# TSOC_PSoC4L.net
KiCad netlist of a schematic drawn in EAGLE
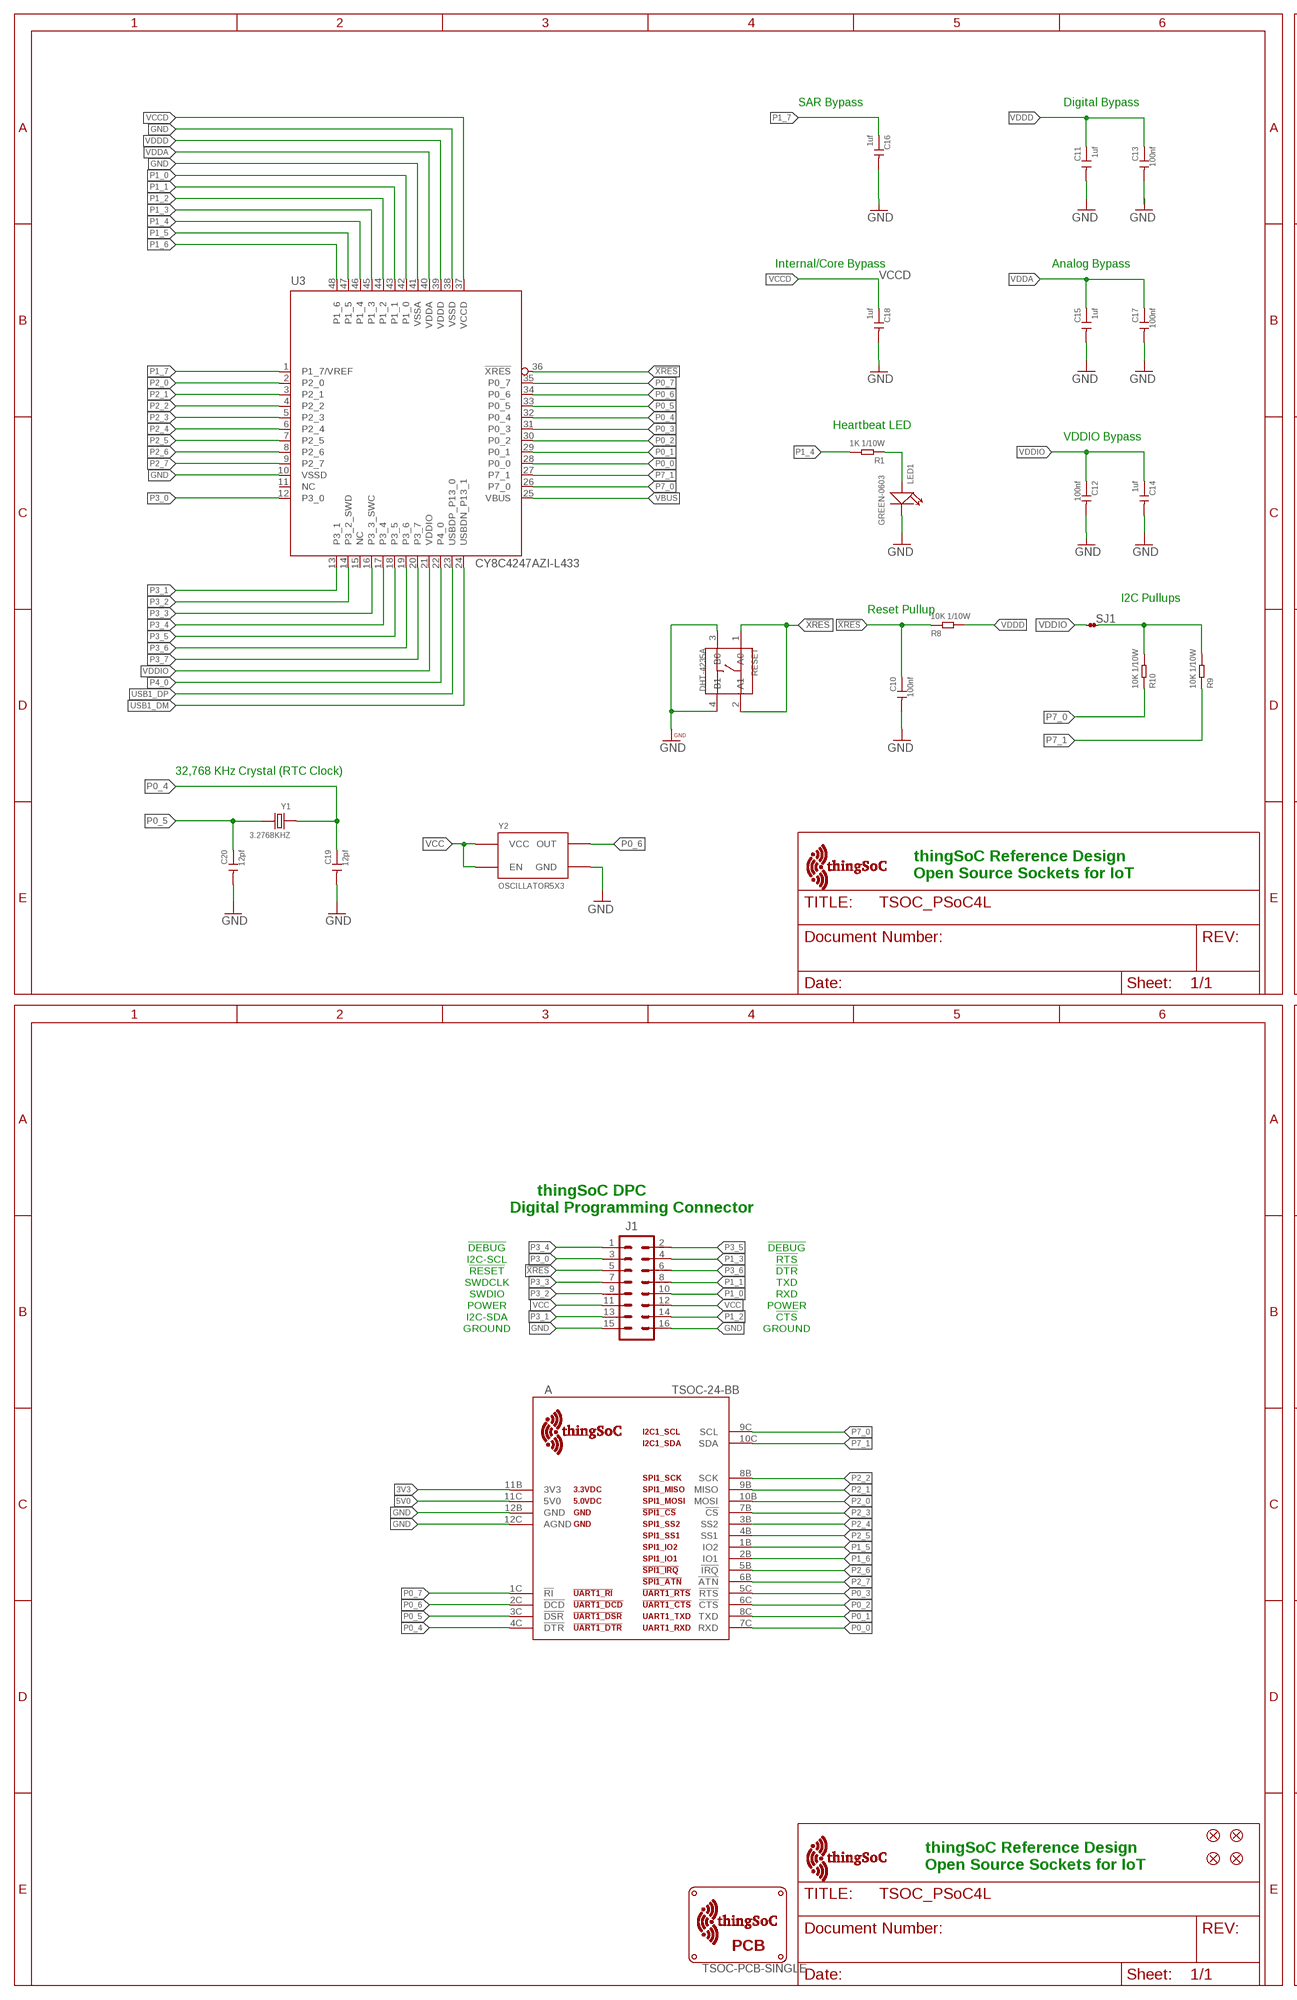
[diagram p0: schematic, sheet 1, part 1 of 2]
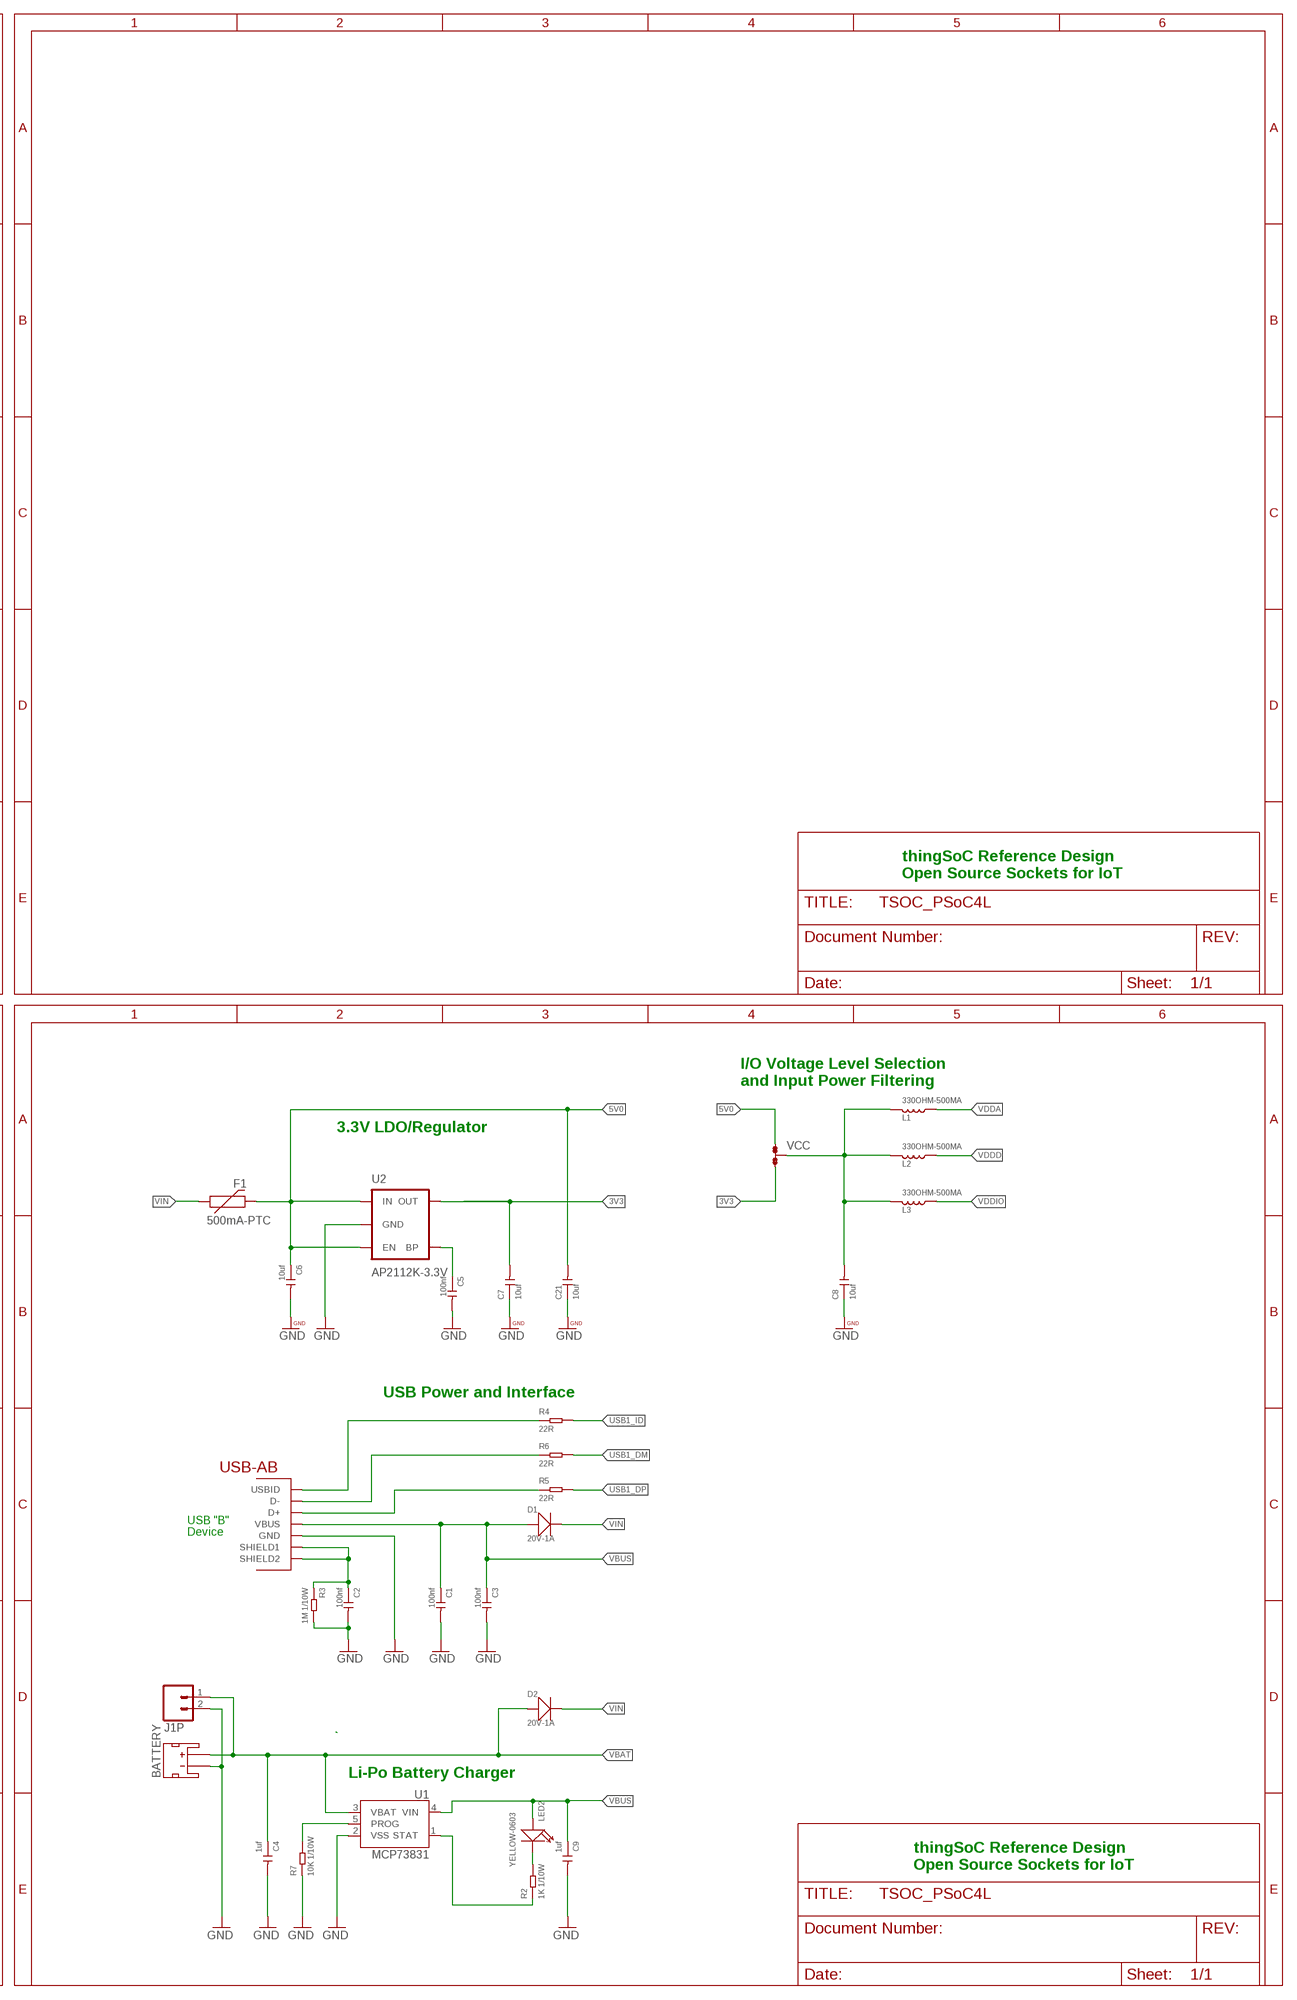
[diagram p1: schematic, sheet 1, part 2 of 2]

(export (version "E")
  (design (tool "Eeschema 10.0.6"))
  (components
    (comp (ref "A")
      (value "TSOC-24-BB")
      (footprint "eagle-import:TSOC-BB-S24")
      (libsource (lib "eagle-import") (part "TSOC-24-BB"))
    )
    (comp (ref "BATTERY")
      (value "JST_2MM_MALE")
      (footprint "eagle-import:JST-2-SMD")
      (libsource (lib "eagle-import") (part "JST_2MM_MALE"))
    )
    (comp (ref "C1")
      (value "100nf")
      (footprint "eagle-import:C0603")
      (fields (field (name "MPN") "CC0603KRX7R9BB104"))
      (libsource (lib "eagle-import") (part "CERAMIC-100NF-50V-10%-X7R(0603)"))
    )
    (comp (ref "C2")
      (value "100nf")
      (footprint "eagle-import:C0603")
      (fields (field (name "MPN") "CC0603KRX7R9BB104"))
      (libsource (lib "eagle-import") (part "CERAMIC-100NF-50V-10%-X7R(0603)"))
    )
    (comp (ref "C3")
      (value "100nf")
      (footprint "eagle-import:C0603")
      (fields (field (name "MPN") "CC0603KRX7R9BB104"))
      (libsource (lib "eagle-import") (part "CERAMIC-100NF-50V-10%-X7R(0603)"))
    )
    (comp (ref "C4")
      (value "1uf")
      (footprint "eagle-import:C0603")
      (fields (field (name "MPN") "CC0603KRX7R8BB105"))
      (libsource (lib "eagle-import") (part "CERAMIC-1UF-25V-10%-X7R(0603)"))
    )
    (comp (ref "C5")
      (value "100nf")
      (footprint "eagle-import:C0603")
      (fields (field (name "MPN") "CC0603KRX7R9BB104"))
      (libsource (lib "eagle-import") (part "CERAMIC-100NF-50V-10%-X7R(0603)"))
    )
    (comp (ref "C6")
      (value "10uf")
      (footprint "eagle-import:C0603")
      (fields (field (name "MPN") "CC0603KRX5R6BB106"))
      (libsource (lib "eagle-import") (part "CERAMIC-10UF-10V-10%-X5R(0603)"))
    )
    (comp (ref "C7")
      (value "10uf")
      (footprint "eagle-import:C0603")
      (fields (field (name "MPN") "CC0603KRX5R6BB106"))
      (libsource (lib "eagle-import") (part "CERAMIC-10UF-10V-10%-X5R(0603)"))
    )
    (comp (ref "C8")
      (value "10uf")
      (footprint "eagle-import:C0603")
      (fields (field (name "MPN") "CC0603KRX5R6BB106"))
      (libsource (lib "eagle-import") (part "CERAMIC-10UF-10V-10%-X5R(0603)"))
    )
    (comp (ref "C9")
      (value "1uf")
      (footprint "eagle-import:C0603")
      (fields (field (name "MPN") "CC0603KRX7R8BB105"))
      (libsource (lib "eagle-import") (part "CERAMIC-1UF-25V-10%-X7R(0603)"))
    )
    (comp (ref "C10")
      (value "100nf")
      (footprint "eagle-import:C0603")
      (fields (field (name "MPN") "CC0603KRX7R9BB104"))
      (libsource (lib "eagle-import") (part "CERAMIC-100NF-50V-10%-X7R(0603)"))
    )
    (comp (ref "C11")
      (value "1uf")
      (footprint "eagle-import:C0603")
      (fields (field (name "MPN") "CC0603KRX7R8BB105"))
      (libsource (lib "eagle-import") (part "CERAMIC-1UF-25V-10%-X7R(0603)"))
    )
    (comp (ref "C12")
      (value "100nf")
      (footprint "eagle-import:C0603")
      (fields (field (name "MPN") "CC0603KRX7R9BB104"))
      (libsource (lib "eagle-import") (part "CERAMIC-100NF-50V-10%-X7R(0603)"))
    )
    (comp (ref "C13")
      (value "100nf")
      (footprint "eagle-import:C0603")
      (fields (field (name "MPN") "CC0603KRX7R9BB104"))
      (libsource (lib "eagle-import") (part "CERAMIC-100NF-50V-10%-X7R(0603)"))
    )
    (comp (ref "C14")
      (value "1uf")
      (footprint "eagle-import:C0603")
      (fields (field (name "MPN") "CC0603KRX7R8BB105"))
      (libsource (lib "eagle-import") (part "CERAMIC-1UF-25V-10%-X7R(0603)"))
    )
    (comp (ref "C15")
      (value "1uf")
      (footprint "eagle-import:C0603")
      (fields (field (name "MPN") "CC0603KRX7R8BB105"))
      (libsource (lib "eagle-import") (part "CERAMIC-1UF-25V-10%-X7R(0603)"))
    )
    (comp (ref "C16")
      (value "1uf")
      (footprint "eagle-import:C0603")
      (fields (field (name "MPN") "CC0603KRX7R8BB105"))
      (libsource (lib "eagle-import") (part "CERAMIC-1UF-25V-10%-X7R(0603)"))
    )
    (comp (ref "C17")
      (value "100nf")
      (footprint "eagle-import:C0603")
      (fields (field (name "MPN") "CC0603KRX7R9BB104"))
      (libsource (lib "eagle-import") (part "CERAMIC-100NF-50V-10%-X7R(0603)"))
    )
    (comp (ref "C18")
      (value "1uf")
      (footprint "eagle-import:C0603")
      (fields (field (name "MPN") "CC0603KRX7R8BB105"))
      (libsource (lib "eagle-import") (part "CERAMIC-1UF-25V-10%-X7R(0603)"))
    )
    (comp (ref "C19")
      (value "12pf")
      (footprint "eagle-import:C0603")
      (fields (field (name "MPN") "CC0603JRNPO9BN120"))
      (libsource (lib "eagle-import") (part "CERAMIC-12PF-50V-5%-NPO(0603)"))
    )
    (comp (ref "C20")
      (value "12pf")
      (footprint "eagle-import:C0603")
      (fields (field (name "MPN") "CC0603JRNPO9BN120"))
      (libsource (lib "eagle-import") (part "CERAMIC-12PF-50V-5%-NPO(0603)"))
    )
    (comp (ref "C21")
      (value "10uf")
      (footprint "eagle-import:C0603")
      (fields (field (name "MPN") "CC0603KRX5R6BB106"))
      (libsource (lib "eagle-import") (part "CERAMIC-10UF-10V-10%-X5R(0603)"))
    )
    (comp (ref "D1")
      (value "20V-1A")
      (footprint "eagle-import:SOD-123")
      (fields (field (name "MPN") "B5819W"))
      (libsource (lib "eagle-import") (part "SMD-DIODE-SCHOTTKY-20V-1A(SOD-123)"))
    )
    (comp (ref "D2")
      (value "20V-1A")
      (footprint "eagle-import:SOD-123")
      (fields (field (name "MPN") "B5819W"))
      (libsource (lib "eagle-import") (part "SMD-DIODE-SCHOTTKY-20V-1A(SOD-123)"))
    )
    (comp (ref "F1")
      (value "500mA-PTC")
      (footprint "eagle-import:PTC-1206")
      (libsource (lib "eagle-import") (part "PTCSMD"))
    )
    (comp (ref "FID1")
      (value "FIDUCIALUFIDUCIAL")
      (footprint "eagle-import:MICRO-FIDUCIAL")
      (libsource (lib "eagle-import") (part "FIDUCIALUFIDUCIAL"))
    )
    (comp (ref "FID2")
      (value "FIDUCIALUFIDUCIAL")
      (footprint "eagle-import:MICRO-FIDUCIAL")
      (libsource (lib "eagle-import") (part "FIDUCIALUFIDUCIAL"))
    )
    (comp (ref "FID3")
      (value "FIDUCIALUFIDUCIAL")
      (footprint "eagle-import:MICRO-FIDUCIAL")
      (libsource (lib "eagle-import") (part "FIDUCIALUFIDUCIAL"))
    )
    (comp (ref "FID4")
      (value "FIDUCIALUFIDUCIAL")
      (footprint "eagle-import:MICRO-FIDUCIAL")
      (libsource (lib "eagle-import") (part "FIDUCIALUFIDUCIAL"))
    )
    (comp (ref "J1")
      (value "M08X2")
      (footprint "eagle-import:2X8")
      (libsource (lib "eagle-import") (part "M08X2"))
    )
    (comp (ref "J1P")
      (value "M02-JST-2-PTH-NO_SILK")
      (footprint "eagle-import:JST-2-PTH-NS")
      (libsource (lib "eagle-import") (part "M02-JST-2-PTH-NO_SILK"))
    )
    (comp (ref "L1")
      (value "330OHM-500MA")
      (footprint "eagle-import:L0603")
      (fields (field (name "MPN") "BLM18AG121SN1D"))
      (libsource (lib "eagle-import") (part "SMD-FERRITE-CHIP-120-OHM-500MA(0603)"))
    )
    (comp (ref "L2")
      (value "330OHM-500MA")
      (footprint "eagle-import:L0603")
      (fields (field (name "MPN") "BLM18AG121SN1D"))
      (libsource (lib "eagle-import") (part "SMD-FERRITE-CHIP-120-OHM-500MA(0603)"))
    )
    (comp (ref "L3")
      (value "330OHM-500MA")
      (footprint "eagle-import:L0603")
      (fields (field (name "MPN") "BLM18AG121SN1D"))
      (libsource (lib "eagle-import") (part "SMD-FERRITE-CHIP-120-OHM-500MA(0603)"))
    )
    (comp (ref "LED1")
      (value "GREEN-0603")
      (footprint "eagle-import:LED-0603")
      (fields (field (name "MPN") "19-217-G7C-AN1P2-3T"))
      (libsource (lib "eagle-import") (part "SMD-LED-CLEAR-GREEN(0603)"))
    )
    (comp (ref "LED2")
      (value "YELLOW-0603")
      (footprint "eagle-import:LED-0603")
      (fields (field (name "MPN") "19-217-Y5C-AM1N1VY-3T"))
      (libsource (lib "eagle-import") (part "SMD-LED-CLEAR-YELLOW(0603)"))
    )
    (comp (ref "R1")
      (value "1K 1/10W")
      (footprint "eagle-import:R0603")
      (fields (field (name "MPN") "RC0603JR-071KL"))
      (libsource (lib "eagle-import") (part "SMD-RES-1K-5%-1/10W(0603)"))
    )
    (comp (ref "R2")
      (value "1K 1/10W")
      (footprint "eagle-import:R0603")
      (fields (field (name "MPN") "RC0603JR-071KL"))
      (libsource (lib "eagle-import") (part "SMD-RES-1K-5%-1/10W(0603)"))
    )
    (comp (ref "R3")
      (value "1M 1/10W")
      (footprint "eagle-import:R0603")
      (fields (field (name "MPN") "RC0603JR-071ML"))
      (libsource (lib "eagle-import") (part "SMD-RES-1M-5%-1/10W(0603)"))
    )
    (comp (ref "R4")
      (value "22R")
      (footprint "eagle-import:R0603")
      (fields (field (name "MPN") "RC0603JR-0722RL"))
      (libsource (lib "eagle-import") (part "SMD-RES-22R-5%-1/10W(0603)"))
    )
    (comp (ref "R5")
      (value "22R")
      (footprint "eagle-import:R0603")
      (fields (field (name "MPN") "RC0603JR-0722RL"))
      (libsource (lib "eagle-import") (part "SMD-RES-22R-5%-1/10W(0603)"))
    )
    (comp (ref "R6")
      (value "22R")
      (footprint "eagle-import:R0603")
      (fields (field (name "MPN") "RC0603JR-0722RL"))
      (libsource (lib "eagle-import") (part "SMD-RES-22R-5%-1/10W(0603)"))
    )
    (comp (ref "R7")
      (value "10K 1/10W")
      (footprint "eagle-import:R0603")
      (fields (field (name "MPN") "RC0603JR-0710KL"))
      (libsource (lib "eagle-import") (part "SMD-RES-10K-5%-1/10W(0603)"))
    )
    (comp (ref "R8")
      (value "10K 1/10W")
      (footprint "eagle-import:R0603")
      (fields (field (name "MPN") "RC0603JR-0710KL"))
      (libsource (lib "eagle-import") (part "SMD-RES-10K-5%-1/10W(0603)"))
    )
    (comp (ref "R9")
      (value "10K 1/10W")
      (footprint "eagle-import:R0603")
      (fields (field (name "MPN") "RC0603JR-0710KL"))
      (libsource (lib "eagle-import") (part "SMD-RES-10K-5%-1/10W(0603)"))
    )
    (comp (ref "R10")
      (value "10K 1/10W")
      (footprint "eagle-import:R0603")
      (fields (field (name "MPN") "RC0603JR-0710KL"))
      (libsource (lib "eagle-import") (part "SMD-RES-10K-5%-1/10W(0603)"))
    )
    (comp (ref "RESET")
      (value "DHT-4235A")
      (footprint "eagle-import:SW4-SMD-4.2X3.2X2.5MM")
      (libsource (lib "eagle-import") (part "SMD-BUTTON-TOP-DHT-4235A(4P-4.2X3.2MM)"))
    )
    (comp (ref "SJ1")
      (value "JMP-2-NC")
      (footprint "eagle-import:JMP-2-NC")
      (libsource (lib "eagle-import") (part "JMP-2-NC"))
    )
    (comp (ref "U$6")
      (value "TSOC-PCB-SINGLE")
      (footprint "eagle-import:TSOC-BB-BRD-DIM")
      (libsource (lib "eagle-import") (part "TSOC-PCB-SINGLE"))
    )
    (comp (ref "U$100")
      (value "TSOC-LOGO-SMALL")
      (footprint "eagle-import:TSOC-LOGO-SML")
      (libsource (lib "eagle-import") (part "TSOC-LOGO-SMALL"))
    )
    (comp (ref "U$101")
      (value "TSOC-LOGO-LRG")
      (footprint "eagle-import:TSOC-LOGO-LRG")
      (libsource (lib "eagle-import") (part "TSOC-LOGO-LRG"))
    )
    (comp (ref "U1")
      (value "MCP73831")
      (footprint "eagle-import:SOT23-5")
      (libsource (lib "eagle-import") (part "MCP73831"))
    )
    (comp (ref "U2")
      (value "AP2112K-3.3V")
      (footprint "eagle-import:SOT23-5")
      (libsource (lib "eagle-import") (part "V_REG_LDOSMD"))
    )
    (comp (ref "U3")
      (value "CY8C4247AZI-L433")
      (footprint "eagle-import:TQFP-7X7-48")
      (libsource (lib "eagle-import") (part "CY8C4247AZI-L433"))
    )
    (comp (ref "USB")
      (value "USB_AB")
      (footprint "eagle-import:USB-AB-MICRO-SMD")
      (libsource (lib "eagle-import") (part "USB_AB"))
    )
    (comp (ref "VCC")
      (value "JMP-3-1_2")
      (footprint "eagle-import:JMP-3-1_2")
      (libsource (lib "eagle-import") (part "JMP-3-1_2"))
    )
    (comp (ref "Y1")
      (value "3.2768KHZ")
      (footprint "eagle-import:X2-SMD-L2.0X1.2X0.55MM")
      (fields (field (name "MPN") "FC-12M"))
      (libsource (lib "eagle-import") (part "SMD-CRYSTAL-32.768KHZ-12.5PF-20PPM-90K(2P-L2.0X1.2MM)"))
    )
    (comp (ref "Y2")
      (value "OSCILLATOR5X3")
      (footprint "eagle-import:CRYSTAL-SMD-5X3")
      (libsource (lib "eagle-import") (part "OSCILLATOR5X3"))
    )
  )
  (nets
    (net (code "1") (name "/~{XRES}") (class "Default")
      (node (ref "C10") (pin "1") (pinfunction "1_1") (pintype "passive"))
      (node (ref "J1") (pin "5") (pinfunction "5_5") (pintype "passive"))
      (node (ref "R8") (pin "1") (pinfunction "1_1") (pintype "passive"))
      (node (ref "RESET") (pin "1") (pinfunction "A0_1") (pintype "bidirectional"))
      (node (ref "RESET") (pin "2") (pinfunction "A1_2") (pintype "bidirectional"))
      (node (ref "U3") (pin "36") (pinfunction "~{XRES}_36") (pintype "bidirectional"))
    )
    (net (code "2") (name "3V3") (class "Default")
      (node (ref "A") (pin "11B") (pinfunction "3V3_11B") (pintype "bidirectional"))
      (node (ref "C7") (pin "2") (pinfunction "2_2") (pintype "passive"))
      (node (ref "U2") (pin "5") (pinfunction "OUT_5") (pintype "passive"))
      (node (ref "VCC") (pin "3") (pinfunction "3_3") (pintype "passive"))
    )
    (net (code "3") (name "5V0") (class "Default")
      (node (ref "A") (pin "11C") (pinfunction "5V0_11C") (pintype "bidirectional"))
      (node (ref "C21") (pin "2") (pinfunction "2_2") (pintype "passive"))
      (node (ref "C6") (pin "1") (pinfunction "1_1") (pintype "passive"))
      (node (ref "F1") (pin "2") (pinfunction "2_2") (pintype "bidirectional"))
      (node (ref "U2") (pin "1") (pinfunction "IN_1") (pintype "input"))
      (node (ref "U2") (pin "3") (pinfunction "EN_3") (pintype "input"))
      (node (ref "VCC") (pin "1") (pinfunction "1_1") (pintype "passive"))
    )
    (net (code "4") (name "GND") (class "Default")
      (node (ref "A") (pin "12B") (pinfunction "GND_12B") (pintype "bidirectional"))
      (node (ref "A") (pin "12C") (pinfunction "AGND_12C") (pintype "bidirectional"))
      (node (ref "BATTERY") (pin "1") (pinfunction "-_1") (pintype "bidirectional"))
      (node (ref "C1") (pin "2") (pinfunction "2_2") (pintype "passive"))
      (node (ref "C10") (pin "2") (pinfunction "2_2") (pintype "passive"))
      (node (ref "C11") (pin "2") (pinfunction "2_2") (pintype "passive"))
      (node (ref "C12") (pin "2") (pinfunction "2_2") (pintype "passive"))
      (node (ref "C13") (pin "2") (pinfunction "2_2") (pintype "passive"))
      (node (ref "C14") (pin "2") (pinfunction "2_2") (pintype "passive"))
      (node (ref "C15") (pin "2") (pinfunction "2_2") (pintype "passive"))
      (node (ref "C16") (pin "2") (pinfunction "2_2") (pintype "passive"))
      (node (ref "C17") (pin "2") (pinfunction "2_2") (pintype "passive"))
      (node (ref "C18") (pin "2") (pinfunction "2_2") (pintype "passive"))
      (node (ref "C19") (pin "2") (pinfunction "2_2") (pintype "passive"))
      (node (ref "C2") (pin "2") (pinfunction "2_2") (pintype "passive"))
      (node (ref "C20") (pin "2") (pinfunction "2_2") (pintype "passive"))
      (node (ref "C21") (pin "1") (pinfunction "1_1") (pintype "passive"))
      (node (ref "C3") (pin "2") (pinfunction "2_2") (pintype "passive"))
      (node (ref "C4") (pin "2") (pinfunction "2_2") (pintype "passive"))
      (node (ref "C5") (pin "2") (pinfunction "2_2") (pintype "passive"))
      (node (ref "C6") (pin "2") (pinfunction "2_2") (pintype "passive"))
      (node (ref "C7") (pin "1") (pinfunction "1_1") (pintype "passive"))
      (node (ref "C8") (pin "1") (pinfunction "1_1") (pintype "passive"))
      (node (ref "C9") (pin "2") (pinfunction "2_2") (pintype "passive"))
      (node (ref "J1") (pin "15") (pinfunction "15_15") (pintype "passive"))
      (node (ref "J1") (pin "16") (pinfunction "16_16") (pintype "passive"))
      (node (ref "J1P") (pin "2") (pinfunction "2_2") (pintype "passive"))
      (node (ref "LED1") (pin "-") (pinfunction "-_-") (pintype "passive"))
      (node (ref "R3") (pin "2") (pinfunction "2_2") (pintype "passive"))
      (node (ref "R7") (pin "1") (pinfunction "1_1") (pintype "passive"))
      (node (ref "RESET") (pin "3") (pinfunction "B0_3") (pintype "bidirectional"))
      (node (ref "RESET") (pin "4") (pinfunction "B1_4") (pintype "bidirectional"))
      (node (ref "U1") (pin "2") (pinfunction "VSS_2") (pintype "power_in"))
      (node (ref "U2") (pin "2") (pinfunction "GND_2") (pintype "input"))
      (node (ref "U3") (pin "10") (pinfunction "VSSD_10") (pintype "bidirectional"))
      (node (ref "U3") (pin "38") (pinfunction "VSSD_38") (pintype "bidirectional"))
      (node (ref "U3") (pin "41") (pinfunction "VSSA_41") (pintype "bidirectional"))
      (node (ref "USB") (pin "GND") (pinfunction "GND_GND") (pintype "bidirectional"))
      (node (ref "Y2") (pin "2") (pinfunction "GND_2") (pintype "bidirectional"))
    )
    (net (code "5") (name "Net-(C2-Pad1)") (class "Default")
      (node (ref "C2") (pin "1") (pinfunction "1_1") (pintype "passive"))
      (node (ref "R3") (pin "1") (pinfunction "1_1") (pintype "passive"))
      (node (ref "USB") (pin "SHIELD1") (pinfunction "SHIELD1_SHIELD1") (pintype "bidirectional"))
      (node (ref "USB") (pin "SHIELD2") (pinfunction "SHIELD2_SHIELD2") (pintype "bidirectional"))
    )
    (net (code "6") (name "Net-(LED1-Pad+)") (class "Default")
      (node (ref "LED1") (pin "+") (pinfunction "+_+") (pintype "passive"))
      (node (ref "R1") (pin "1") (pinfunction "1_1") (pintype "passive"))
    )
    (net (code "7") (name "Net-(LED2-Pad-)") (class "Default")
      (node (ref "LED2") (pin "-") (pinfunction "-_-") (pintype "passive"))
      (node (ref "R2") (pin "2") (pinfunction "2_2") (pintype "passive"))
    )
    (net (code "8") (name "Net-(R5-Pad1)") (class "Default")
      (node (ref "R5") (pin "1") (pinfunction "1_1") (pintype "passive"))
      (node (ref "USB") (pin "D+") (pinfunction "D+_D+") (pintype "bidirectional"))
    )
    (net (code "9") (name "Net-(R6-Pad1)") (class "Default")
      (node (ref "R6") (pin "1") (pinfunction "1_1") (pintype "passive"))
      (node (ref "USB") (pin "D-") (pinfunction "D-_D-") (pintype "bidirectional"))
    )
    (net (code "10") (name "Net-(R10-Pad2)") (class "Default")
      (node (ref "R10") (pin "2") (pinfunction "2_2") (pintype "passive"))
      (node (ref "R9") (pin "2") (pinfunction "2_2") (pintype "passive"))
      (node (ref "SJ1") (pin "2") (pinfunction "2_2") (pintype "passive"))
    )
    (net (code "11") (name "Net-(U1-PROG)") (class "Default")
      (node (ref "R7") (pin "2") (pinfunction "2_2") (pintype "passive"))
      (node (ref "U1") (pin "5") (pinfunction "PROG_5") (pintype "input"))
    )
    (net (code "12") (name "Net-(U1-STAT)") (class "Default")
      (node (ref "R2") (pin "1") (pinfunction "1_1") (pintype "passive"))
      (node (ref "U1") (pin "1") (pinfunction "STAT_1") (pintype "output"))
    )
    (net (code "13") (name "Net-(U2-BP)") (class "Default")
      (node (ref "C5") (pin "1") (pinfunction "1_1") (pintype "passive"))
      (node (ref "U2") (pin "4") (pinfunction "BP_4") (pintype "input"))
    )
    (net (code "14") (name "Net-(USB-USBID)") (class "Default")
      (node (ref "R4") (pin "1") (pinfunction "1_1") (pintype "passive"))
      (node (ref "USB") (pin "ID") (pinfunction "USBID_ID") (pintype "bidirectional"))
    )
    (net (code "15") (name "P0_0") (class "Default")
      (node (ref "A") (pin "7C") (pinfunction "RXD_7C") (pintype "bidirectional"))
      (node (ref "U3") (pin "28") (pinfunction "P0_0_28") (pintype "bidirectional"))
    )
    (net (code "16") (name "P0_1") (class "Default")
      (node (ref "A") (pin "8C") (pinfunction "TXD_8C") (pintype "bidirectional"))
      (node (ref "U3") (pin "29") (pinfunction "P0_1_29") (pintype "bidirectional"))
    )
    (net (code "17") (name "P0_2") (class "Default")
      (node (ref "A") (pin "6C") (pinfunction "~{CTS}_6C") (pintype "bidirectional"))
      (node (ref "U3") (pin "30") (pinfunction "P0_2_30") (pintype "input"))
    )
    (net (code "18") (name "P0_3") (class "Default")
      (node (ref "A") (pin "5C") (pinfunction "~{RTS}_5C") (pintype "bidirectional"))
      (node (ref "U3") (pin "31") (pinfunction "P0_3_31") (pintype "bidirectional"))
    )
    (net (code "19") (name "P0_4") (class "Default")
      (node (ref "A") (pin "4C") (pinfunction "~{DTR}_4C") (pintype "bidirectional"))
      (node (ref "C19") (pin "1") (pinfunction "1_1") (pintype "passive"))
      (node (ref "U3") (pin "32") (pinfunction "P0_4_32") (pintype "bidirectional"))
      (node (ref "Y1") (pin "1") (pinfunction "1_1") (pintype "passive"))
    )
    (net (code "20") (name "P0_5") (class "Default")
      (node (ref "A") (pin "3C") (pinfunction "~{DSR}_3C") (pintype "bidirectional"))
      (node (ref "C20") (pin "1") (pinfunction "1_1") (pintype "passive"))
      (node (ref "U3") (pin "33") (pinfunction "P0_5_33") (pintype "bidirectional"))
      (node (ref "Y1") (pin "2") (pinfunction "2_2") (pintype "passive"))
    )
    (net (code "21") (name "P0_6") (class "Default")
      (node (ref "A") (pin "2C") (pinfunction "~{DCD}_2C") (pintype "bidirectional"))
      (node (ref "U3") (pin "34") (pinfunction "P0_6_34") (pintype "power_in"))
      (node (ref "Y2") (pin "3") (pinfunction "OUT_3") (pintype "bidirectional"))
    )
    (net (code "22") (name "P0_7") (class "Default")
      (node (ref "A") (pin "1C") (pinfunction "~{RI}_1C") (pintype "bidirectional"))
      (node (ref "U3") (pin "35") (pinfunction "P0_7_35") (pintype "bidirectional"))
    )
    (net (code "23") (name "P1_0") (class "Default")
      (node (ref "J1") (pin "10") (pinfunction "10_10") (pintype "passive"))
      (node (ref "U3") (pin "42") (pinfunction "P1_0_42") (pintype "bidirectional"))
    )
    (net (code "24") (name "P1_1") (class "Default")
      (node (ref "J1") (pin "8") (pinfunction "8_8") (pintype "passive"))
      (node (ref "U3") (pin "43") (pinfunction "P1_1_43") (pintype "bidirectional"))
    )
    (net (code "25") (name "P1_2") (class "Default")
      (node (ref "J1") (pin "14") (pinfunction "14_14") (pintype "passive"))
      (node (ref "U3") (pin "44") (pinfunction "P1_2_44") (pintype "power_in"))
    )
    (net (code "26") (name "P1_3") (class "Default")
      (node (ref "J1") (pin "4") (pinfunction "4_4") (pintype "passive"))
      (node (ref "U3") (pin "45") (pinfunction "P1_3_45") (pintype "bidirectional"))
    )
    (net (code "27") (name "P1_4") (class "Default")
      (node (ref "R1") (pin "2") (pinfunction "2_2") (pintype "passive"))
      (node (ref "U3") (pin "46") (pinfunction "P1_4_46") (pintype "bidirectional"))
    )
    (net (code "28") (name "P1_5") (class "Default")
      (node (ref "A") (pin "1B") (pinfunction "IO2_1B") (pintype "bidirectional"))
      (node (ref "U3") (pin "47") (pinfunction "P1_5_47") (pintype "bidirectional"))
    )
    (net (code "29") (name "P1_6") (class "Default")
      (node (ref "A") (pin "2B") (pinfunction "IO1_2B") (pintype "bidirectional"))
      (node (ref "U3") (pin "48") (pinfunction "P1_6_48") (pintype "bidirectional"))
    )
    (net (code "30") (name "P1_7") (class "Default")
      (node (ref "C16") (pin "1") (pinfunction "1_1") (pintype "passive"))
      (node (ref "U3") (pin "1") (pinfunction "P1_7/VREF_1") (pintype "bidirectional"))
    )
    (net (code "31") (name "P2_0") (class "Default")
      (node (ref "A") (pin "10B") (pinfunction "MOSI_10B") (pintype "bidirectional"))
      (node (ref "U3") (pin "2") (pinfunction "P2_0_2") (pintype "bidirectional"))
    )
    (net (code "32") (name "P2_1") (class "Default")
      (node (ref "A") (pin "9B") (pinfunction "MISO_9B") (pintype "bidirectional"))
      (node (ref "U3") (pin "3") (pinfunction "P2_1_3") (pintype "bidirectional"))
    )
    (net (code "33") (name "P2_2") (class "Default")
      (node (ref "A") (pin "8B") (pinfunction "SCK_8B") (pintype "bidirectional"))
      (node (ref "U3") (pin "4") (pinfunction "P2_2_4") (pintype "power_in"))
    )
    (net (code "34") (name "P2_3") (class "Default")
      (node (ref "A") (pin "7B") (pinfunction "~{CS}_7B") (pintype "bidirectional"))
      (node (ref "U3") (pin "5") (pinfunction "P2_3_5") (pintype "bidirectional"))
    )
    (net (code "35") (name "P2_4") (class "Default")
      (node (ref "A") (pin "3B") (pinfunction "SS2_3B") (pintype "bidirectional"))
      (node (ref "U3") (pin "6") (pinfunction "P2_4_6") (pintype "bidirectional"))
    )
    (net (code "36") (name "P2_5") (class "Default")
      (node (ref "A") (pin "4B") (pinfunction "SS1_4B") (pintype "bidirectional"))
      (node (ref "U3") (pin "7") (pinfunction "P2_5_7") (pintype "bidirectional"))
    )
    (net (code "37") (name "P2_6") (class "Default")
      (node (ref "A") (pin "5B") (pinfunction "~{IRQ}_5B") (pintype "bidirectional"))
      (node (ref "U3") (pin "8") (pinfunction "P2_6_8") (pintype "power_in"))
    )
    (net (code "38") (name "P2_7") (class "Default")
      (node (ref "A") (pin "6B") (pinfunction "~{ATN}_6B") (pintype "bidirectional"))
      (node (ref "U3") (pin "9") (pinfunction "P2_7_9") (pintype "bidirectional"))
    )
    (net (code "39") (name "P3_0") (class "Default")
      (node (ref "J1") (pin "3") (pinfunction "3_3") (pintype "passive"))
      (node (ref "U3") (pin "12") (pinfunction "P3_0_12") (pintype "bidirectional"))
    )
    (net (code "40") (name "P3_1") (class "Default")
      (node (ref "J1") (pin "13") (pinfunction "13_13") (pintype "passive"))
      (node (ref "U3") (pin "13") (pinfunction "P3_1_13") (pintype "bidirectional"))
    )
    (net (code "41") (name "P3_2") (class "Default")
      (node (ref "J1") (pin "9") (pinfunction "9_9") (pintype "passive"))
      (node (ref "U3") (pin "14") (pinfunction "P3_2_SWD_14") (pintype "bidirectional"))
    )
    (net (code "42") (name "P3_3") (class "Default")
      (node (ref "J1") (pin "7") (pinfunction "7_7") (pintype "passive"))
      (node (ref "U3") (pin "16") (pinfunction "P3_3_SWC_16") (pintype "bidirectional"))
    )
    (net (code "43") (name "P3_4") (class "Default")
      (node (ref "J1") (pin "1") (pinfunction "1_1") (pintype "passive"))
      (node (ref "U3") (pin "17") (pinfunction "P3_4_17") (pintype "bidirectional"))
    )
    (net (code "44") (name "P3_5") (class "Default")
      (node (ref "J1") (pin "2") (pinfunction "2_2") (pintype "passive"))
      (node (ref "U3") (pin "18") (pinfunction "P3_5_18") (pintype "bidirectional"))
    )
    (net (code "45") (name "P3_6") (class "Default")
      (node (ref "J1") (pin "6") (pinfunction "6_6") (pintype "passive"))
      (node (ref "U3") (pin "19") (pinfunction "P3_6_19") (pintype "power_in"))
    )
    (net (code "46") (name "P3_7") (class "Default")
      (node (ref "U3") (pin "20") (pinfunction "P3_7_20") (pintype "bidirectional"))
    )
    (net (code "47") (name "P4_0") (class "Default")
      (node (ref "U3") (pin "22") (pinfunction "P4_0_22") (pintype "bidirectional"))
    )
    (net (code "48") (name "P7_0") (class "Default")
      (node (ref "A") (pin "9C") (pinfunction "SCL_9C") (pintype "bidirectional"))
      (node (ref "R10") (pin "1") (pinfunction "1_1") (pintype "passive"))
      (node (ref "U3") (pin "26") (pinfunction "P7_0_26") (pintype "bidirectional"))
    )
    (net (code "49") (name "P7_1") (class "Default")
      (node (ref "A") (pin "10C") (pinfunction "SDA_10C") (pintype "bidirectional"))
      (node (ref "R9") (pin "1") (pinfunction "1_1") (pintype "passive"))
      (node (ref "U3") (pin "27") (pinfunction "P7_1_27") (pintype "bidirectional"))
    )
    (net (code "50") (name "USB1_DM") (class "Default")
      (node (ref "R6") (pin "2") (pinfunction "2_2") (pintype "passive"))
      (node (ref "U3") (pin "24") (pinfunction "USBDN_P13_1_24") (pintype "bidirectional"))
    )
    (net (code "51") (name "USB1_DP") (class "Default")
      (node (ref "R5") (pin "2") (pinfunction "2_2") (pintype "passive"))
      (node (ref "U3") (pin "23") (pinfunction "USBDP_P13_0_23") (pintype "bidirectional"))
    )
    (net (code "52") (name "USB1_ID") (class "Default")
      (node (ref "R4") (pin "2") (pinfunction "2_2") (pintype "passive"))
    )
    (net (code "53") (name "VBAT") (class "Default")
      (node (ref "BATTERY") (pin "2") (pinfunction "+_2") (pintype "bidirectional"))
      (node (ref "C4") (pin "1") (pinfunction "1_1") (pintype "passive"))
      (node (ref "D2") (pin "+") (pinfunction "+_+") (pintype "passive"))
      (node (ref "J1P") (pin "1") (pinfunction "1_1") (pintype "passive"))
      (node (ref "U1") (pin "3") (pinfunction "VBAT_3") (pintype "power_in"))
    )
    (net (code "54") (name "VBUS") (class "Default")
      (node (ref "C1") (pin "1") (pinfunction "1_1") (pintype "passive"))
      (node (ref "C3") (pin "1") (pinfunction "1_1") (pintype "passive"))
      (node (ref "C9") (pin "1") (pinfunction "1_1") (pintype "passive"))
      (node (ref "D1") (pin "+") (pinfunction "+_+") (pintype "passive"))
      (node (ref "LED2") (pin "+") (pinfunction "+_+") (pintype "passive"))
      (node (ref "U1") (pin "4") (pinfunction "VIN_4") (pintype "power_in"))
      (node (ref "U3") (pin "25") (pinfunction "VBUS_25") (pintype "bidirectional"))
      (node (ref "USB") (pin "VBUS") (pinfunction "VBUS_VBUS") (pintype "bidirectional"))
    )
    (net (code "55") (name "VCC") (class "Default")
      (node (ref "C8") (pin "2") (pinfunction "2_2") (pintype "passive"))
      (node (ref "J1") (pin "11") (pinfunction "11_11") (pintype "passive"))
      (node (ref "J1") (pin "12") (pinfunction "12_12") (pintype "passive"))
      (node (ref "L1") (pin "1") (pinfunction "1_1") (pintype "passive"))
      (node (ref "L2") (pin "1") (pinfunction "1_1") (pintype "passive"))
      (node (ref "L3") (pin "1") (pinfunction "1_1") (pintype "passive"))
      (node (ref "VCC") (pin "2") (pinfunction "2_2") (pintype "passive"))
      (node (ref "Y2") (pin "1") (pinfunction "EN_1") (pintype "bidirectional"))
      (node (ref "Y2") (pin "4") (pinfunction "VCC_4") (pintype "bidirectional"))
    )
    (net (code "56") (name "VCCD") (class "Default")
      (node (ref "C18") (pin "1") (pinfunction "1_1") (pintype "passive"))
      (node (ref "U3") (pin "37") (pinfunction "VCCD_37") (pintype "bidirectional"))
    )
    (net (code "57") (name "VDDA") (class "Default")
      (node (ref "C15") (pin "1") (pinfunction "1_1") (pintype "passive"))
      (node (ref "C17") (pin "1") (pinfunction "1_1") (pintype "passive"))
      (node (ref "L1") (pin "2") (pinfunction "2_2") (pintype "passive"))
      (node (ref "U3") (pin "40") (pinfunction "VDDA_40") (pintype "bidirectional"))
    )
    (net (code "58") (name "VDDD") (class "Default")
      (node (ref "C11") (pin "1") (pinfunction "1_1") (pintype "passive"))
      (node (ref "C13") (pin "1") (pinfunction "1_1") (pintype "passive"))
      (node (ref "L2") (pin "2") (pinfunction "2_2") (pintype "passive"))
      (node (ref "R8") (pin "2") (pinfunction "2_2") (pintype "passive"))
      (node (ref "U3") (pin "39") (pinfunction "VDDD_39") (pintype "bidirectional"))
    )
    (net (code "59") (name "VDDIO") (class "Default")
      (node (ref "C12") (pin "1") (pinfunction "1_1") (pintype "passive"))
      (node (ref "C14") (pin "1") (pinfunction "1_1") (pintype "passive"))
      (node (ref "L3") (pin "2") (pinfunction "2_2") (pintype "passive"))
      (node (ref "SJ1") (pin "1") (pinfunction "1_1") (pintype "passive"))
      (node (ref "U3") (pin "21") (pinfunction "VDDIO_21") (pintype "bidirectional"))
    )
    (net (code "60") (name "VIN") (class "Default")
      (node (ref "D1") (pin "-") (pinfunction "-_-") (pintype "passive"))
      (node (ref "D2") (pin "-") (pinfunction "-_-") (pintype "passive"))
      (node (ref "F1") (pin "1") (pinfunction "1_1") (pintype "bidirectional"))
    )
    (net (code "61") (name "unconnected-(BATTERY-PAD1-PadNC1)") (class "Default")
      (node (ref "BATTERY") (pin "NC1") (pinfunction "PAD1_NC1") (pintype "bidirectional"))
    )
    (net (code "62") (name "unconnected-(BATTERY-PAD2-PadNC2)") (class "Default")
      (node (ref "BATTERY") (pin "NC2") (pinfunction "PAD2_NC2") (pintype "bidirectional"))
    )
    (net (code "63") (name "unconnected-(U3-NC-Pad11)") (class "Default")
      (node (ref "U3") (pin "11") (pinfunction "NC_11") (pintype "bidirectional"))
    )
    (net (code "64") (name "unconnected-(U3-NC-Pad15)") (class "Default")
      (node (ref "U3") (pin "15") (pinfunction "NC_15") (pintype "bidirectional"))
    )
  )
)
